# REF-IN-BLE-NS_4-2.net
KiCad netlist of a schematic drawn in EAGLE
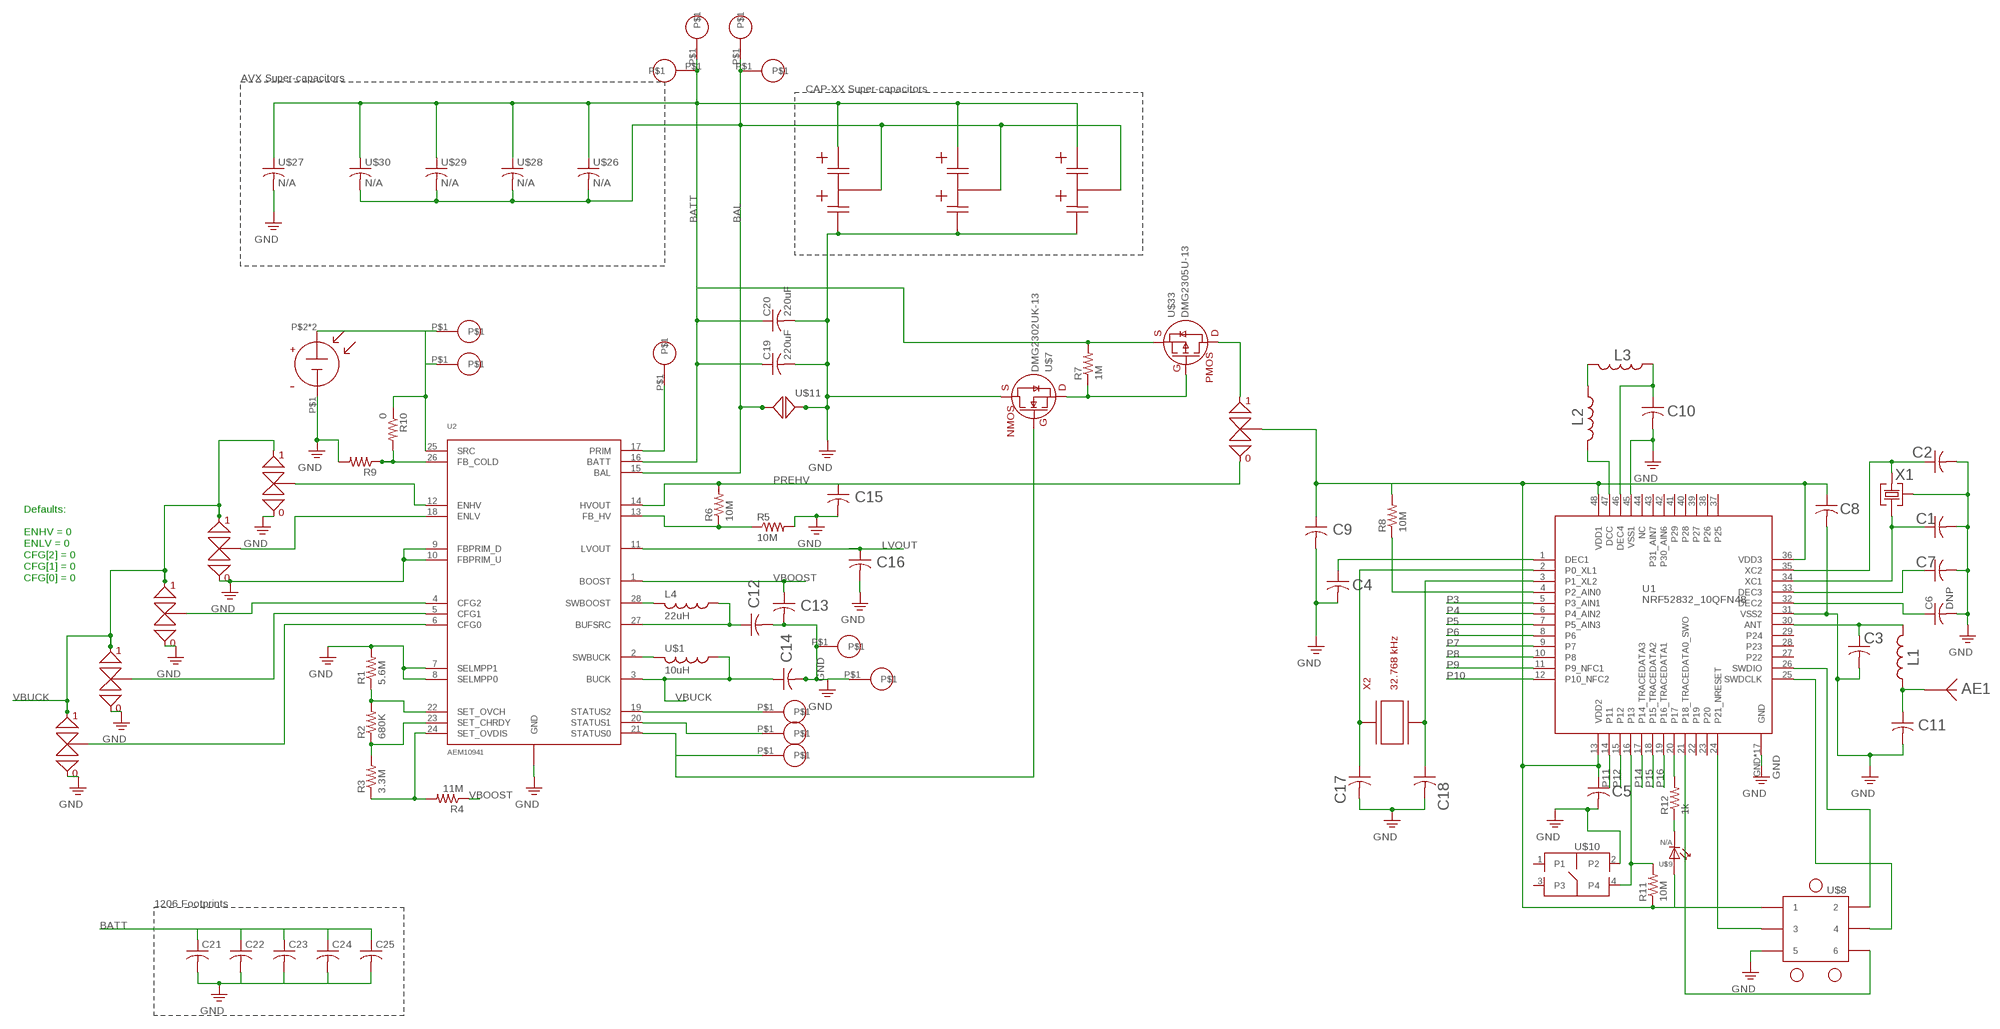
[diagram p0: schematic, sheet 1]

(export (version "E")
  (design (tool "Eeschema 10.0.6"))
  (components
    (comp (ref "AE1")
      (value "2.4GHZ_ANTENNAFLIPPED")
      (footprint "eagle-import:BLE_ANTENNA_NORDIC_FLIPPED")
      (libsource (lib "eagle-import") (part "2.4GHZ_ANTENNAFLIPPED"))
    )
    (comp (ref "C1")
      (value "12pF")
      (footprint "eagle-import:C0603")
      (fields (field (name "MFG_PART#") "C0603C120J5GACTU"))
      (libsource (lib "eagle-import") (part "C-USC0603T-12PF"))
    )
    (comp (ref "C2")
      (value "12pF")
      (footprint "eagle-import:C0603")
      (fields (field (name "MFG_PART#") "C0603C120J5GACTU"))
      (libsource (lib "eagle-import") (part "C-USC0603T-12PF"))
    )
    (comp (ref "C3")
      (value "0.8pF")
      (footprint "eagle-import:C0603")
      (fields (field (name "MFG_PART#") "CBR06C808B5GAC "))
      (libsource (lib "eagle-import") (part "C-USC0603T-0.8PF"))
    )
    (comp (ref "C4")
      (value "100nF")
      (footprint "eagle-import:C0603")
      (fields (field (name "MFG_PART#") "CL10B104KB8NNNC"))
      (libsource (lib "eagle-import") (part "C-USC0603T-100NF"))
    )
    (comp (ref "C5")
      (value "100nF")
      (footprint "eagle-import:C0603")
      (fields (field (name "MFG_PART#") "CL10B104KB8NNNC"))
      (libsource (lib "eagle-import") (part "C-USC0603T-100NF"))
    )
    (comp (ref "C6")
      (value "DNP")
      (footprint "eagle-import:C0603")
      (libsource (lib "eagle-import") (part "C-USC0603"))
    )
    (comp (ref "C7")
      (value "100pF")
      (footprint "eagle-import:C0603")
      (fields (field (name "MFG_PART#") "CL10C101JB8NNNC"))
      (libsource (lib "eagle-import") (part "C-USC0603T-100PF"))
    )
    (comp (ref "C8")
      (value "100nF")
      (footprint "eagle-import:C0603")
      (fields (field (name "MFG_PART#") "CL10B104KB8NNNC"))
      (libsource (lib "eagle-import") (part "C-USC0603T-100NF"))
    )
    (comp (ref "C9")
      (value "4.7uF")
      (footprint "eagle-import:C0603")
      (fields (field (name "MFG_PART#") "CL10A475KQ8NNWC "))
      (libsource (lib "eagle-import") (part "C-USC0603T-4.7UF"))
    )
    (comp (ref "C10")
      (value "1uF")
      (footprint "eagle-import:C0603")
      (fields (field (name "MFG_PART#") "CL10A105KP8NNNC ") (field (name "PERCENTAGE") "10%"))
      (libsource (lib "eagle-import") (part "C-USC0603T-1UF"))
    )
    (comp (ref "C11")
      (value "DNP")
      (footprint "eagle-import:C0603")
      (libsource (lib "eagle-import") (part "C-USC0603"))
    )
    (comp (ref "C12")
      (value "10uF")
      (footprint "eagle-import:C0603")
      (fields (field (name "MFG_PART#") "GRM188R61E106MA73D"))
      (libsource (lib "eagle-import") (part "C-USC0603T-10UF"))
    )
    (comp (ref "C13")
      (value "22uF")
      (footprint "eagle-import:C0603")
      (fields (field (name "MFG_PART#") "GRM188R61A226ME15D"))
      (libsource (lib "eagle-import") (part "C-USC0603T-22UF"))
    )
    (comp (ref "C14")
      (value "10uF")
      (footprint "eagle-import:C0603")
      (fields (field (name "MFG_PART#") "GRM188R61E106MA73D"))
      (libsource (lib "eagle-import") (part "C-USC0603T-10UF"))
    )
    (comp (ref "C15")
      (value "10uF")
      (footprint "eagle-import:C0603")
      (fields (field (name "MFG_PART#") "GRM188R61E106MA73D"))
      (libsource (lib "eagle-import") (part "C-USC0603T-10UF"))
    )
    (comp (ref "C16")
      (value "10uF")
      (footprint "eagle-import:C0603")
      (fields (field (name "MFG_PART#") "GRM188R61E106MA73D"))
      (libsource (lib "eagle-import") (part "C-USC0603T-10UF"))
    )
    (comp (ref "C17")
      (value "12pF")
      (footprint "eagle-import:C0603")
      (fields (field (name "MFG_PART#") "C0603C120J5GACTU"))
      (libsource (lib "eagle-import") (part "C-USC0603T-12PF"))
    )
    (comp (ref "C18")
      (value "12pF")
      (footprint "eagle-import:C0603")
      (fields (field (name "MFG_PART#") "C0603C120J5GACTU"))
      (libsource (lib "eagle-import") (part "C-USC0603T-12PF"))
    )
    (comp (ref "C19")
      (value "220uF")
      (footprint "eagle-import:C1206")
      (fields (field (name "MFG_PART#") "GRM31CC80G227ME11L"))
      (libsource (lib "eagle-import") (part "C-USC1206T-220UF"))
    )
    (comp (ref "C20")
      (value "220uF")
      (footprint "eagle-import:C1206")
      (fields (field (name "MFG_PART#") "GRM31CC80G227ME11L"))
      (libsource (lib "eagle-import") (part "C-USC1206T-220UF"))
    )
    (comp (ref "C21")
      (value "C-USC1206")
      (footprint "eagle-import:C1206")
      (libsource (lib "eagle-import") (part "C-USC1206"))
    )
    (comp (ref "C22")
      (value "C-USC1206")
      (footprint "eagle-import:C1206")
      (libsource (lib "eagle-import") (part "C-USC1206"))
    )
    (comp (ref "C23")
      (value "C-USC1206")
      (footprint "eagle-import:C1206")
      (libsource (lib "eagle-import") (part "C-USC1206"))
    )
    (comp (ref "C24")
      (value "C-USC1206")
      (footprint "eagle-import:C1206")
      (libsource (lib "eagle-import") (part "C-USC1206"))
    )
    (comp (ref "C25")
      (value "C-USC1206")
      (footprint "eagle-import:C1206")
      (libsource (lib "eagle-import") (part "C-USC1206"))
    )
    (comp (ref "L1")
      (value "3.9nH")
      (footprint "eagle-import:L0603")
      (fields (field (name "MFG_PART#") "L-14C3N9SV4T "))
      (libsource (lib "eagle-import") (part "L0603V-3.9NH"))
    )
    (comp (ref "L2")
      (value "10uH")
      (footprint "eagle-import:L0603")
      (fields (field (name "MFG_PART#") "LBR2012T100M"))
      (libsource (lib "eagle-import") (part "L0603V-10UH"))
    )
    (comp (ref "L3")
      (value "15nH")
      (footprint "eagle-import:L0603")
      (fields (field (name "MFG_PART#") "L-14C15NJV4T"))
      (libsource (lib "eagle-import") (part "L0603V-15NH"))
    )
    (comp (ref "L4")
      (value "22uH")
      (footprint "eagle-import:744031220")
      (fields (field (name "MFG_PART#") "744031220"))
      (libsource (lib "eagle-import") (part "744031220"))
    )
    (comp (ref "R1")
      (value "5.6M")
      (footprint "eagle-import:R0603")
      (libsource (lib "eagle-import") (part "R-US_R0603"))
    )
    (comp (ref "R2")
      (value "680K")
      (footprint "eagle-import:R0603")
      (libsource (lib "eagle-import") (part "R-US_R0603"))
    )
    (comp (ref "R3")
      (value "3.3M")
      (footprint "eagle-import:R0603")
      (libsource (lib "eagle-import") (part "R-US_R0603"))
    )
    (comp (ref "R4")
      (value "11M")
      (footprint "eagle-import:R0603")
      (libsource (lib "eagle-import") (part "R-US_R0603"))
    )
    (comp (ref "R5")
      (value "10M")
      (footprint "eagle-import:R0603")
      (libsource (lib "eagle-import") (part "R-US_R0603"))
    )
    (comp (ref "R6")
      (value "10M")
      (footprint "eagle-import:R0603")
      (libsource (lib "eagle-import") (part "R-US_R0603"))
    )
    (comp (ref "R7")
      (value "1M")
      (footprint "eagle-import:R0603")
      (libsource (lib "eagle-import") (part "R-US_R0603"))
    )
    (comp (ref "R8")
      (value "10M")
      (footprint "eagle-import:R0603")
      (libsource (lib "eagle-import") (part "R-US_R0603"))
    )
    (comp (ref "R9")
      (value "R-US_R0603")
      (footprint "eagle-import:R0603")
      (libsource (lib "eagle-import") (part "R-US_R0603"))
    )
    (comp (ref "R10")
      (value "0")
      (footprint "eagle-import:R0603")
      (libsource (lib "eagle-import") (part "R-US_R0603"))
    )
    (comp (ref "R11")
      (value "10M")
      (footprint "eagle-import:R0603")
      (libsource (lib "eagle-import") (part "R-US_R0603"))
    )
    (comp (ref "R12")
      (value "1k")
      (footprint "eagle-import:R0603")
      (libsource (lib "eagle-import") (part "R-US_R0603"))
    )
    (comp (ref "U$1")
      (value "10uH")
      (footprint "eagle-import:L0603")
      (fields (field (name "MFG_PART#") "LBR2012T100M"))
      (libsource (lib "eagle-import") (part "L0603V-10UH"))
    )
    (comp (ref "U$2")
      (value "DOUBLE_SOLDER_BRIDGE0_PASTED")
      (footprint "eagle-import:DOUBLE_SOLDER_BRIDGE_0_PASTED")
      (libsource (lib "eagle-import") (part "DOUBLE_SOLDER_BRIDGE0_PASTED"))
    )
    (comp (ref "U$3")
      (value "DOUBLE_SOLDER_BRIDGE0_PASTED")
      (footprint "eagle-import:DOUBLE_SOLDER_BRIDGE_0_PASTED")
      (libsource (lib "eagle-import") (part "DOUBLE_SOLDER_BRIDGE0_PASTED"))
    )
    (comp (ref "U$4")
      (value "DOUBLE_SOLDER_BRIDGE0_PASTED")
      (footprint "eagle-import:DOUBLE_SOLDER_BRIDGE_0_PASTED")
      (libsource (lib "eagle-import") (part "DOUBLE_SOLDER_BRIDGE0_PASTED"))
    )
    (comp (ref "U$5")
      (value "DOUBLE_SOLDER_BRIDGE0_PASTED")
      (footprint "eagle-import:DOUBLE_SOLDER_BRIDGE_0_PASTED")
      (libsource (lib "eagle-import") (part "DOUBLE_SOLDER_BRIDGE0_PASTED"))
    )
    (comp (ref "U$6")
      (value "DOUBLE_SOLDER_BRIDGE0_PASTED")
      (footprint "eagle-import:DOUBLE_SOLDER_BRIDGE_0_PASTED")
      (libsource (lib "eagle-import") (part "DOUBLE_SOLDER_BRIDGE0_PASTED"))
    )
    (comp (ref "U$7")
      (value "DMG2302UK-13")
      (footprint "eagle-import:SOT-23-3-DIODESINC")
      (libsource (lib "eagle-import") (part "DMG2302UK-13"))
    )
    (comp (ref "U$8")
      (value "N/A")
      (footprint "eagle-import:TC2030-IDC")
      (libsource (lib "eagle-import") (part "TC2030-IDC"))
    )
    (comp (ref "U$9")
      (value "N/A")
      (footprint "eagle-import:APT1608LZGCK")
      (fields (field (name "MFG_PART#") "APT1608LZGCK"))
      (libsource (lib "eagle-import") (part "APT1608LZGCK"))
    )
    (comp (ref "U$10")
      (value "MJTP1140")
      (footprint "eagle-import:MJTP1140A")
      (fields (field (name "MFG_PART#") "TL3315NF100Q "))
      (libsource (lib "eagle-import") (part "MJTP1140"))
    )
    (comp (ref "U$11")
      (value "SOLDER_BRIGDECLOSED")
      (footprint "eagle-import:SOLDER_BRIDGE_CLOSED")
      (libsource (lib "eagle-import") (part "SOLDER_BRIGDECLOSED"))
    )
    (comp (ref "U$12")
      (value "N/A")
      (footprint "eagle-import:1MM_PAD")
      (libsource (lib "eagle-import") (part "1MM_PAD"))
    )
    (comp (ref "U$13")
      (value "N/A")
      (footprint "eagle-import:1MM_PAD")
      (libsource (lib "eagle-import") (part "1MM_PAD"))
    )
    (comp (ref "U$14")
      (value "N/A")
      (footprint "eagle-import:1MM_PAD")
      (libsource (lib "eagle-import") (part "1MM_PAD"))
    )
    (comp (ref "U$15")
      (value "N/A")
      (footprint "eagle-import:1MM_PAD")
      (libsource (lib "eagle-import") (part "1MM_PAD"))
    )
    (comp (ref "U$16")
      (value "N/A")
      (footprint "eagle-import:SOLAR_CELL_37X54MM")
      (libsource (lib "eagle-import") (part "SOLAR_CELL_LL200-2.4-37"))
    )
    (comp (ref "U$17")
      (value "N/A")
      (footprint "eagle-import:1MM_PAD")
      (libsource (lib "eagle-import") (part "1MM_PAD"))
    )
    (comp (ref "U$18")
      (value "N/A")
      (footprint "eagle-import:1MM_PAD")
      (libsource (lib "eagle-import") (part "1MM_PAD"))
    )
    (comp (ref "U$19")
      (value "N/A")
      (footprint "eagle-import:1MM_PAD")
      (libsource (lib "eagle-import") (part "1MM_PAD"))
    )
    (comp (ref "U$23")
      (value "N/A")
      (footprint "eagle-import:CAP-XX_A-TYPE")
      (libsource (lib "eagle-import") (part "CAP-XX_A-TYPE"))
    )
    (comp (ref "U$24")
      (value "N/A")
      (footprint "eagle-import:CAP-XX_S-TYPE")
      (libsource (lib "eagle-import") (part "CAP-XX_S-TYPE"))
    )
    (comp (ref "U$25")
      (value "N/A")
      (footprint "eagle-import:CAP-XX_W-TYPE")
      (libsource (lib "eagle-import") (part "CAP-XX_W-TYPE"))
    )
    (comp (ref "U$26")
      (value "N/A")
      (footprint "eagle-import:BZ01_L-TYPE")
      (libsource (lib "eagle-import") (part "BZ01_L-TYPE"))
    )
    (comp (ref "U$27")
      (value "N/A")
      (footprint "eagle-import:BZ059_N-TYPE")
      (libsource (lib "eagle-import") (part "BZ059_N-TYPE"))
    )
    (comp (ref "U$28")
      (value "N/A")
      (footprint "eagle-import:BZ01_S-TYPE")
      (libsource (lib "eagle-import") (part "BZ01_S-TYPE"))
    )
    (comp (ref "U$29")
      (value "N/A")
      (footprint "eagle-import:BZ05_S-TYPE")
      (libsource (lib "eagle-import") (part "BZ05_S-TYPE"))
    )
    (comp (ref "U$30")
      (value "N/A")
      (footprint "eagle-import:BZ09_S-TYPE")
      (libsource (lib "eagle-import") (part "BZ09_S-TYPE"))
    )
    (comp (ref "U$31")
      (value "DOUBLE_SOLDER_BRIDGE1_PASTED")
      (footprint "eagle-import:DOUBLE_SOLDER_BRIDGE_1_PASTED")
      (libsource (lib "eagle-import") (part "DOUBLE_SOLDER_BRIDGE1_PASTED"))
    )
    (comp (ref "U$33")
      (value "DMG2305U-13")
      (footprint "eagle-import:SOT-23-3-DIODESINC")
      (libsource (lib "eagle-import") (part "DMG2305U-13"))
    )
    (comp (ref "U$35")
      (value "N/A")
      (footprint "eagle-import:1MM_PAD")
      (libsource (lib "eagle-import") (part "1MM_PAD"))
    )
    (comp (ref "U$36")
      (value "N/A")
      (footprint "eagle-import:1MM_PAD")
      (libsource (lib "eagle-import") (part "1MM_PAD"))
    )
    (comp (ref "U$39")
      (value "N/A")
      (footprint "eagle-import:1MM_PAD")
      (libsource (lib "eagle-import") (part "1MM_PAD"))
    )
    (comp (ref "U$40")
      (value "N/A")
      (footprint "eagle-import:1MM_PAD")
      (libsource (lib "eagle-import") (part "1MM_PAD"))
    )
    (comp (ref "U$41")
      (value "N/A")
      (footprint "eagle-import:1MM_PAD")
      (libsource (lib "eagle-import") (part "1MM_PAD"))
    )
    (comp (ref "U1")
      (value "NRF52832_10QFN48")
      (footprint "eagle-import:NRF52832_10")
      (fields (field (name "MFG_PART#") "NRF52832-QFAA-R"))
      (libsource (lib "eagle-import") (part "NRF52832_10QFN48"))
    )
    (comp (ref "U2")
      (value "AEM10941")
      (footprint "eagle-import:QFN28_5X5_05PITCH")
      (fields (field (name "MFG_PART#") "AEM10941-QFN "))
      (libsource (lib "eagle-import") (part "AEM10941"))
    )
    (comp (ref "X1")
      (value "32 MHz")
      (footprint "eagle-import:FA-128-EPSON")
      (fields (field (name "MFG_PART#") "FA-128 32.0000MF10Z-AJ3"))
      (libsource (lib "eagle-import") (part "FA-128-32MHZMF10Z-AJ5"))
    )
    (comp (ref "X2")
      (value "32.768 kHz")
      (footprint "eagle-import:FC-135")
      (fields (field (name "MFG_PART#") "FC-135 32.7680KA-AC"))
      (libsource (lib "eagle-import") (part "FC-135_32.7680KA-AC"))
    )
  )
  (nets
    (net (code "1") (name "/BAL") (class "Default")
      (node (ref "U$11") (pin "P$1") (pinfunction "P1_P$1") (pintype "bidirectional"))
      (node (ref "U$19") (pin "P$1") (pinfunction "P$1_P$1") (pintype "bidirectional"))
      (node (ref "U$23") (pin "P$1") (pinfunction "BAL_P$1") (pintype "bidirectional"))
      (node (ref "U$24") (pin "P$1") (pinfunction "BAL_P$1") (pintype "bidirectional"))
      (node (ref "U$25") (pin "P$1") (pinfunction "BAL_P$1") (pintype "bidirectional"))
      (node (ref "U$26") (pin "P$3") (pinfunction "2_P$3") (pintype "passive"))
      (node (ref "U$26") (pin "P$4") (pinfunction "2_P$4") (pintype "passive"))
      (node (ref "U$28") (pin "P$3") (pinfunction "2_P$3") (pintype "passive"))
      (node (ref "U$29") (pin "P$3") (pinfunction "2_P$3") (pintype "passive"))
      (node (ref "U$30") (pin "P$3") (pinfunction "2_P$3") (pintype "passive"))
      (node (ref "U$41") (pin "P$1") (pinfunction "P$1_P$1") (pintype "bidirectional"))
      (node (ref "U2") (pin "15") (pinfunction "BAL_15") (pintype "bidirectional"))
    )
    (net (code "2") (name "/BATT") (class "Default")
      (node (ref "C19") (pin "1") (pinfunction "1_1") (pintype "passive"))
      (node (ref "C20") (pin "1") (pinfunction "1_1") (pintype "passive"))
      (node (ref "C21") (pin "1") (pinfunction "1_1") (pintype "passive"))
      (node (ref "C22") (pin "1") (pinfunction "1_1") (pintype "passive"))
      (node (ref "C23") (pin "1") (pinfunction "1_1") (pintype "passive"))
      (node (ref "C24") (pin "1") (pinfunction "1_1") (pintype "passive"))
      (node (ref "C25") (pin "1") (pinfunction "1_1") (pintype "passive"))
      (node (ref "R7") (pin "2") (pinfunction "2_2") (pintype "passive"))
      (node (ref "U$18") (pin "P$1") (pinfunction "P$1_P$1") (pintype "bidirectional"))
      (node (ref "U$23") (pin "P$2") (pinfunction "+_P$2") (pintype "bidirectional"))
      (node (ref "U$24") (pin "P$2") (pinfunction "+_P$2") (pintype "bidirectional"))
      (node (ref "U$25") (pin "P$2") (pinfunction "+_P$2") (pintype "bidirectional"))
      (node (ref "U$26") (pin "P$1") (pinfunction "1_P$1") (pintype "passive"))
      (node (ref "U$26") (pin "P$2") (pinfunction "1_P$2") (pintype "passive"))
      (node (ref "U$27") (pin "P$1") (pinfunction "1_P$1") (pintype "passive"))
      (node (ref "U$28") (pin "P$1") (pinfunction "1_P$1") (pintype "passive"))
      (node (ref "U$28") (pin "P$2") (pinfunction "1_P$2") (pintype "passive"))
      (node (ref "U$29") (pin "P$1") (pinfunction "1_P$1") (pintype "passive"))
      (node (ref "U$29") (pin "P$2") (pinfunction "1_P$2") (pintype "passive"))
      (node (ref "U$30") (pin "P$1") (pinfunction "1_P$1") (pintype "passive"))
      (node (ref "U$30") (pin "P$2") (pinfunction "1_P$2") (pintype "passive"))
      (node (ref "U$33") (pin "2") (pinfunction "S_2") (pintype "bidirectional"))
      (node (ref "U$40") (pin "P$1") (pinfunction "P$1_P$1") (pintype "bidirectional"))
      (node (ref "U2") (pin "16") (pinfunction "BATT_16") (pintype "bidirectional"))
    )
    (net (code "3") (name "/LVOUT") (class "Default")
      (node (ref "C16") (pin "1") (pinfunction "1_1") (pintype "passive"))
      (node (ref "U2") (pin "11") (pinfunction "LVOUT_11") (pintype "output"))
    )
    (net (code "4") (name "/P3") (class "Default")
      (node (ref "U1") (pin "5") (pinfunction "P3_AIN1_5") (pintype "bidirectional"))
    )
    (net (code "5") (name "/P4") (class "Default")
      (node (ref "U1") (pin "6") (pinfunction "P4_AIN2_6") (pintype "bidirectional"))
    )
    (net (code "6") (name "/P5") (class "Default")
      (node (ref "U1") (pin "7") (pinfunction "P5_AIN3_7") (pintype "bidirectional"))
    )
    (net (code "7") (name "/P6") (class "Default")
      (node (ref "U1") (pin "8") (pinfunction "P6_8") (pintype "bidirectional"))
    )
    (net (code "8") (name "/P7") (class "Default")
      (node (ref "U1") (pin "9") (pinfunction "P7_9") (pintype "bidirectional"))
    )
    (net (code "9") (name "/P8") (class "Default")
      (node (ref "U1") (pin "10") (pinfunction "P8_10") (pintype "bidirectional"))
    )
    (net (code "10") (name "/P9") (class "Default")
      (node (ref "U1") (pin "11") (pinfunction "P9_NFC1_11") (pintype "bidirectional"))
    )
    (net (code "11") (name "/P10") (class "Default")
      (node (ref "U1") (pin "12") (pinfunction "P10_NFC2_12") (pintype "bidirectional"))
    )
    (net (code "12") (name "/P11") (class "Default")
      (node (ref "U1") (pin "14") (pinfunction "P11_14") (pintype "bidirectional"))
    )
    (net (code "13") (name "/P12") (class "Default")
      (node (ref "U1") (pin "15") (pinfunction "P12_15") (pintype "bidirectional"))
    )
    (net (code "14") (name "/P14") (class "Default")
      (node (ref "U1") (pin "17") (pinfunction "P14_TRACEDATA3_17") (pintype "bidirectional"))
    )
    (net (code "15") (name "/P15") (class "Default")
      (node (ref "U1") (pin "18") (pinfunction "P15_TRACEDATA2_18") (pintype "bidirectional"))
    )
    (net (code "16") (name "/P16") (class "Default")
      (node (ref "U1") (pin "19") (pinfunction "P16_TRACEDATA1_19") (pintype "bidirectional"))
    )
    (net (code "17") (name "/PREHV") (class "Default")
      (node (ref "C15") (pin "1") (pinfunction "1_1") (pintype "passive"))
      (node (ref "R6") (pin "2") (pinfunction "2_2") (pintype "passive"))
      (node (ref "U$31") (pin "IN0") (pinfunction "IN0_IN0") (pintype "bidirectional"))
      (node (ref "U2") (pin "14") (pinfunction "HVOUT_14") (pintype "output"))
    )
    (net (code "18") (name "/VBOOST") (class "Default")
      (node (ref "C13") (pin "1") (pinfunction "1_1") (pintype "passive"))
      (node (ref "R4") (pin "1") (pinfunction "1_1") (pintype "passive"))
      (node (ref "U2") (pin "1") (pinfunction "BOOST_1") (pintype "bidirectional"))
    )
    (net (code "19") (name "/VBUCK") (class "Default")
      (node (ref "C14") (pin "1") (pinfunction "1_1") (pintype "passive"))
      (node (ref "U$1") (pin "1") (pinfunction "1_1") (pintype "passive"))
      (node (ref "U$2") (pin "IN1") (pinfunction "IN1_IN1") (pintype "bidirectional"))
      (node (ref "U$3") (pin "IN1") (pinfunction "IN1_IN1") (pintype "bidirectional"))
      (node (ref "U$4") (pin "IN1") (pinfunction "IN1_IN1") (pintype "bidirectional"))
      (node (ref "U$5") (pin "IN1") (pinfunction "IN1_IN1") (pintype "bidirectional"))
      (node (ref "U$6") (pin "IN1") (pinfunction "IN1_IN1") (pintype "bidirectional"))
      (node (ref "U2") (pin "3") (pinfunction "BUCK_3") (pintype "bidirectional"))
    )
    (net (code "20") (name "GND") (class "Default")
      (node (ref "C1") (pin "2") (pinfunction "2_2") (pintype "passive"))
      (node (ref "C10") (pin "2") (pinfunction "2_2") (pintype "passive"))
      (node (ref "C11") (pin "2") (pinfunction "2_2") (pintype "passive"))
      (node (ref "C12") (pin "2") (pinfunction "2_2") (pintype "passive"))
      (node (ref "C13") (pin "2") (pinfunction "2_2") (pintype "passive"))
      (node (ref "C14") (pin "2") (pinfunction "2_2") (pintype "passive"))
      (node (ref "C15") (pin "2") (pinfunction "2_2") (pintype "passive"))
      (node (ref "C16") (pin "2") (pinfunction "2_2") (pintype "passive"))
      (node (ref "C17") (pin "2") (pinfunction "2_2") (pintype "passive"))
      (node (ref "C18") (pin "2") (pinfunction "2_2") (pintype "passive"))
      (node (ref "C19") (pin "2") (pinfunction "2_2") (pintype "passive"))
      (node (ref "C2") (pin "2") (pinfunction "2_2") (pintype "passive"))
      (node (ref "C20") (pin "2") (pinfunction "2_2") (pintype "passive"))
      (node (ref "C21") (pin "2") (pinfunction "2_2") (pintype "passive"))
      (node (ref "C22") (pin "2") (pinfunction "2_2") (pintype "passive"))
      (node (ref "C23") (pin "2") (pinfunction "2_2") (pintype "passive"))
      (node (ref "C24") (pin "2") (pinfunction "2_2") (pintype "passive"))
      (node (ref "C25") (pin "2") (pinfunction "2_2") (pintype "passive"))
      (node (ref "C3") (pin "2") (pinfunction "2_2") (pintype "passive"))
      (node (ref "C4") (pin "2") (pinfunction "2_2") (pintype "passive"))
      (node (ref "C5") (pin "2") (pinfunction "2_2") (pintype "passive"))
      (node (ref "C6") (pin "2") (pinfunction "2_2") (pintype "passive"))
      (node (ref "C7") (pin "2") (pinfunction "2_2") (pintype "passive"))
      (node (ref "C8") (pin "2") (pinfunction "2_2") (pintype "passive"))
      (node (ref "C9") (pin "2") (pinfunction "2_2") (pintype "passive"))
      (node (ref "R1") (pin "2") (pinfunction "2_2") (pintype "passive"))
      (node (ref "R5") (pin "2") (pinfunction "2_2") (pintype "passive"))
      (node (ref "R9") (pin "2") (pinfunction "2_2") (pintype "passive"))
      (node (ref "U$10") (pin "2") (pinfunction "P2_2") (pintype "bidirectional"))
      (node (ref "U$11") (pin "P$2") (pinfunction "P2_P$2") (pintype "bidirectional"))
      (node (ref "U$16") (pin "P$1") (pinfunction "GND_P$1") (pintype "bidirectional"))
      (node (ref "U$17") (pin "P$1") (pinfunction "P$1_P$1") (pintype "bidirectional"))
      (node (ref "U$2") (pin "IN0") (pinfunction "IN0_IN0") (pintype "bidirectional"))
      (node (ref "U$23") (pin "P$3") (pinfunction "-_P$3") (pintype "bidirectional"))
      (node (ref "U$24") (pin "P$3") (pinfunction "-_P$3") (pintype "bidirectional"))
      (node (ref "U$25") (pin "P$3") (pinfunction "-_P$3") (pintype "bidirectional"))
      (node (ref "U$27") (pin "P$2") (pinfunction "2_P$2") (pintype "passive"))
      (node (ref "U$3") (pin "IN0") (pinfunction "IN0_IN0") (pintype "bidirectional"))
      (node (ref "U$35") (pin "P$1") (pinfunction "P$1_P$1") (pintype "bidirectional"))
      (node (ref "U$4") (pin "IN0") (pinfunction "IN0_IN0") (pintype "bidirectional"))
      (node (ref "U$5") (pin "IN0") (pinfunction "IN0_IN0") (pintype "bidirectional"))
      (node (ref "U$6") (pin "IN0") (pinfunction "IN0_IN0") (pintype "bidirectional"))
      (node (ref "U$7") (pin "2") (pinfunction "S_2") (pintype "bidirectional"))
      (node (ref "U$8") (pin "P5") (pinfunction "5_P5") (pintype "bidirectional"))
      (node (ref "U1") (pin "31") (pinfunction "VSS2_31") (pintype "bidirectional"))
      (node (ref "U1") (pin "45") (pinfunction "VSS1_45") (pintype "bidirectional"))
      (node (ref "U1") (pin "GND") (pinfunction "GND_GND") (pintype "bidirectional"))
      (node (ref "U1") (pin "P$10") (pinfunction "GND_P$10") (pintype "bidirectional"))
      (node (ref "U1") (pin "P$11") (pinfunction "GND_P$11") (pintype "bidirectional"))
      (node (ref "U1") (pin "P$12") (pinfunction "GND_P$12") (pintype "bidirectional"))
      (node (ref "U1") (pin "P$13") (pinfunction "GND_P$13") (pintype "bidirectional"))
      (node (ref "U1") (pin "P$14") (pinfunction "GND_P$14") (pintype "bidirectional"))
      (node (ref "U1") (pin "P$15") (pinfunction "GND_P$15") (pintype "bidirectional"))
      (node (ref "U1") (pin "P$16") (pinfunction "GND_P$16") (pintype "bidirectional"))
      (node (ref "U1") (pin "P$17") (pinfunction "GND_P$17") (pintype "bidirectional"))
      (node (ref "U1") (pin "P$2") (pinfunction "GND_P$2") (pintype "bidirectional"))
      (node (ref "U1") (pin "P$3") (pinfunction "GND_P$3") (pintype "bidirectional"))
      (node (ref "U1") (pin "P$4") (pinfunction "GND_P$4") (pintype "bidirectional"))
      (node (ref "U1") (pin "P$5") (pinfunction "GND_P$5") (pintype "bidirectional"))
      (node (ref "U1") (pin "P$6") (pinfunction "GND_P$6") (pintype "bidirectional"))
      (node (ref "U1") (pin "P$7") (pinfunction "GND_P$7") (pintype "bidirectional"))
      (node (ref "U1") (pin "P$8") (pinfunction "GND_P$8") (pintype "bidirectional"))
      (node (ref "U1") (pin "P$9") (pinfunction "GND_P$9") (pintype "bidirectional"))
      (node (ref "U2") (pin "10") (pinfunction "FBPRIM_U_10") (pintype "bidirectional"))
      (node (ref "U2") (pin "7") (pinfunction "SELMPP1_7") (pintype "input"))
      (node (ref "U2") (pin "8") (pinfunction "SELMPP0_8") (pintype "input"))
      (node (ref "U2") (pin "9") (pinfunction "FBPRIM_D_9") (pintype "bidirectional"))
      (node (ref "U2") (pin "GND") (pinfunction "GND_GND") (pintype "power_in"))
      (node (ref "U2") (pin "GND1") (pinfunction "GND_GND1") (pintype "power_in"))
      (node (ref "U2") (pin "GND2") (pinfunction "GND_GND2") (pintype "power_in"))
      (node (ref "U2") (pin "GND3") (pinfunction "GND_GND3") (pintype "power_in"))
      (node (ref "U2") (pin "GND4") (pinfunction "GND_GND4") (pintype "power_in"))
      (node (ref "U2") (pin "GND5") (pinfunction "GND_GND5") (pintype "power_in"))
      (node (ref "X1") (pin "P2") (pinfunction "P3_P2") (pintype "bidirectional"))
      (node (ref "X1") (pin "P4") (pinfunction "P3_P4") (pintype "bidirectional"))
    )
    (net (code "21") (name "Net-(AE1-PadP$1)") (class "Default")
      (node (ref "AE1") (pin "P$1") (pinfunction "P$1_P$1") (pintype "bidirectional"))
      (node (ref "C11") (pin "1") (pinfunction "1_1") (pintype "passive"))
      (node (ref "L1") (pin "1") (pinfunction "1_1") (pintype "passive"))
    )
    (net (code "22") (name "Net-(L2-Pad1)") (class "Default")
      (node (ref "L2") (pin "1") (pinfunction "1_1") (pintype "passive"))
      (node (ref "L3") (pin "2") (pinfunction "2_2") (pintype "passive"))
    )
    (net (code "23") (name "Net-(L4-1)") (class "Default")
      (node (ref "C12") (pin "1") (pinfunction "1_1") (pintype "passive"))
      (node (ref "L4") (pin "PIN1") (pinfunction "1_PIN1") (pintype "passive"))
      (node (ref "U2") (pin "27") (pinfunction "BUFSRC_27") (pintype "bidirectional"))
    )
    (net (code "24") (name "Net-(L4-2)") (class "Default")
      (node (ref "L4") (pin "PIN2") (pinfunction "2_PIN2") (pintype "passive"))
      (node (ref "U2") (pin "28") (pinfunction "SWBOOST_28") (pintype "bidirectional"))
    )
    (net (code "25") (name "Net-(R12-Pad1)") (class "Default")
      (node (ref "R12") (pin "1") (pinfunction "1_1") (pintype "passive"))
      (node (ref "U$9") (pin "C") (pinfunction "C_C") (pintype "bidirectional"))
    )
    (net (code "26") (name "Net-(U$7-G)") (class "Default")
      (node (ref "U$15") (pin "P$1") (pinfunction "P$1_P$1") (pintype "bidirectional"))
      (node (ref "U$7") (pin "1") (pinfunction "G_1") (pintype "bidirectional"))
      (node (ref "U2") (pin "21") (pinfunction "STATUS0_21") (pintype "output"))
    )
    (net (code "27") (name "Net-(U$8-1)") (class "Default")
      (node (ref "C5") (pin "1") (pinfunction "1_1") (pintype "passive"))
      (node (ref "C8") (pin "1") (pinfunction "1_1") (pintype "passive"))
      (node (ref "C9") (pin "1") (pinfunction "1_1") (pintype "passive"))
      (node (ref "R11") (pin "1") (pinfunction "1_1") (pintype "passive"))
      (node (ref "R8") (pin "2") (pinfunction "2_2") (pintype "passive"))
      (node (ref "U$31") (pin "OUT") (pinfunction "OUT_OUT") (pintype "bidirectional"))
      (node (ref "U$8") (pin "P1") (pinfunction "1_P1") (pintype "bidirectional"))
      (node (ref "U$9") (pin "A") (pinfunction "A_A") (pintype "bidirectional"))
      (node (ref "U1") (pin "13") (pinfunction "VDD2_13") (pintype "bidirectional"))
      (node (ref "U1") (pin "36") (pinfunction "VDD3_36") (pintype "bidirectional"))
      (node (ref "U1") (pin "48") (pinfunction "VDD1_48") (pintype "bidirectional"))
    )
    (net (code "28") (name "Net-(U$8-2)") (class "Default")
      (node (ref "U$8") (pin "P2") (pinfunction "2_P2") (pintype "bidirectional"))
      (node (ref "U1") (pin "26") (pinfunction "SWDIO_26") (pintype "bidirectional"))
    )
    (net (code "29") (name "Net-(U$8-3)") (class "Default")
      (node (ref "U$8") (pin "P3") (pinfunction "3_P3") (pintype "bidirectional"))
      (node (ref "U1") (pin "24") (pinfunction "P21_NRESET_24") (pintype "bidirectional"))
    )
    (net (code "30") (name "Net-(U$8-4)") (class "Default")
      (node (ref "U$8") (pin "P4") (pinfunction "4_P4") (pintype "bidirectional"))
      (node (ref "U1") (pin "25") (pinfunction "SWDCLK_25") (pintype "bidirectional"))
    )
    (net (code "31") (name "Net-(U$8-6)") (class "Default")
      (node (ref "U$8") (pin "P6") (pinfunction "6_P6") (pintype "bidirectional"))
      (node (ref "U1") (pin "21") (pinfunction "P18_TRACEDATA0_SWO_21") (pintype "bidirectional"))
    )
    (net (code "32") (name "Net-(U$10-P4)") (class "Default")
      (node (ref "R11") (pin "2") (pinfunction "2_2") (pintype "passive"))
      (node (ref "U$10") (pin "4") (pinfunction "P4_4") (pintype "bidirectional"))
      (node (ref "U1") (pin "16") (pinfunction "P13_16") (pintype "bidirectional"))
    )
    (net (code "33") (name "Net-(U$33-D)") (class "Default")
      (node (ref "U$31") (pin "IN1") (pinfunction "IN1_IN1") (pintype "bidirectional"))
      (node (ref "U$33") (pin "3") (pinfunction "D_3") (pintype "bidirectional"))
    )
    (net (code "34") (name "Net-(U$33-G)") (class "Default")
      (node (ref "R7") (pin "1") (pinfunction "1_1") (pintype "passive"))
      (node (ref "U$33") (pin "1") (pinfunction "G_1") (pintype "bidirectional"))
      (node (ref "U$7") (pin "3") (pinfunction "D_3") (pintype "bidirectional"))
    )
    (net (code "35") (name "Net-(U1-ANT)") (class "Default")
      (node (ref "C3") (pin "1") (pinfunction "1_1") (pintype "passive"))
      (node (ref "L1") (pin "2") (pinfunction "2_2") (pintype "passive"))
      (node (ref "U1") (pin "30") (pinfunction "ANT_30") (pintype "bidirectional"))
    )
    (net (code "36") (name "Net-(U1-DCC)") (class "Default")
      (node (ref "L2") (pin "2") (pinfunction "2_2") (pintype "passive"))
      (node (ref "U1") (pin "47") (pinfunction "DCC_47") (pintype "bidirectional"))
    )
    (net (code "37") (name "Net-(U1-DEC1)") (class "Default")
      (node (ref "C4") (pin "1") (pinfunction "1_1") (pintype "passive"))
      (node (ref "U1") (pin "1") (pinfunction "DEC1_1") (pintype "bidirectional"))
    )
    (net (code "38") (name "Net-(U1-DEC2)") (class "Default")
      (node (ref "C6") (pin "1") (pinfunction "1_1") (pintype "passive"))
      (node (ref "U1") (pin "32") (pinfunction "DEC2_32") (pintype "bidirectional"))
    )
    (net (code "39") (name "Net-(U1-DEC3)") (class "Default")
      (node (ref "C7") (pin "1") (pinfunction "1_1") (pintype "passive"))
      (node (ref "U1") (pin "33") (pinfunction "DEC3_33") (pintype "bidirectional"))
    )
    (net (code "40") (name "Net-(U1-DEC4)") (class "Default")
      (node (ref "C10") (pin "1") (pinfunction "1_1") (pintype "passive"))
      (node (ref "L3") (pin "1") (pinfunction "1_1") (pintype "passive"))
      (node (ref "U1") (pin "46") (pinfunction "DEC4_46") (pintype "bidirectional"))
    )
    (net (code "41") (name "Net-(U1-P0_XL1)") (class "Default")
      (node (ref "C17") (pin "1") (pinfunction "1_1") (pintype "passive"))
      (node (ref "U1") (pin "2") (pinfunction "P0_XL1_2") (pintype "bidirectional"))
      (node (ref "X2") (pin "P$1") (pinfunction "P$1_P$1") (pintype "bidirectional"))
    )
    (net (code "42") (name "Net-(U1-P1_XL2)") (class "Default")
      (node (ref "C18") (pin "1") (pinfunction "1_1") (pintype "passive"))
      (node (ref "U1") (pin "3") (pinfunction "P1_XL2_3") (pintype "bidirectional"))
      (node (ref "X2") (pin "P$2") (pinfunction "P$2_P$2") (pintype "bidirectional"))
    )
    (net (code "43") (name "Net-(U1-P2_AIN0)") (class "Default")
      (node (ref "R8") (pin "1") (pinfunction "1_1") (pintype "passive"))
      (node (ref "U1") (pin "4") (pinfunction "P2_AIN0_4") (pintype "bidirectional"))
    )
    (net (code "44") (name "Net-(U1-P17)") (class "Default")
      (node (ref "R12") (pin "2") (pinfunction "2_2") (pintype "passive"))
      (node (ref "U1") (pin "20") (pinfunction "P17_20") (pintype "bidirectional"))
    )
    (net (code "45") (name "Net-(U1-XC1)") (class "Default")
      (node (ref "C1") (pin "1") (pinfunction "1_1") (pintype "passive"))
      (node (ref "U1") (pin "34") (pinfunction "XC1_34") (pintype "bidirectional"))
      (node (ref "X1") (pin "P3") (pinfunction "1_P3") (pintype "passive"))
    )
    (net (code "46") (name "Net-(U1-XC2)") (class "Default")
      (node (ref "C2") (pin "1") (pinfunction "1_1") (pintype "passive"))
      (node (ref "U1") (pin "35") (pinfunction "XC2_35") (pintype "bidirectional"))
      (node (ref "X1") (pin "P1") (pinfunction "2_P1") (pintype "passive"))
    )
    (net (code "47") (name "Net-(U2-CFG0)") (class "Default")
      (node (ref "U$6") (pin "OUT") (pinfunction "OUT_OUT") (pintype "bidirectional"))
      (node (ref "U2") (pin "6") (pinfunction "CFG0_6") (pintype "input"))
    )
    (net (code "48") (name "Net-(U2-CFG1)") (class "Default")
      (node (ref "U$5") (pin "OUT") (pinfunction "OUT_OUT") (pintype "bidirectional"))
      (node (ref "U2") (pin "5") (pinfunction "CFG1_5") (pintype "input"))
    )
    (net (code "49") (name "Net-(U2-CFG2)") (class "Default")
      (node (ref "U$4") (pin "OUT") (pinfunction "OUT_OUT") (pintype "bidirectional"))
      (node (ref "U2") (pin "4") (pinfunction "CFG2_4") (pintype "input"))
    )
    (net (code "50") (name "Net-(U2-ENHV)") (class "Default")
      (node (ref "U$2") (pin "OUT") (pinfunction "OUT_OUT") (pintype "bidirectional"))
      (node (ref "U2") (pin "12") (pinfunction "ENHV_12") (pintype "input"))
    )
    (net (code "51") (name "Net-(U2-ENLV)") (class "Default")
      (node (ref "U$3") (pin "OUT") (pinfunction "OUT_OUT") (pintype "bidirectional"))
      (node (ref "U2") (pin "18") (pinfunction "ENLV_18") (pintype "input"))
    )
    (net (code "52") (name "Net-(U2-FB_COLD)") (class "Default")
      (node (ref "R10") (pin "2") (pinfunction "2_2") (pintype "passive"))
      (node (ref "R9") (pin "1") (pinfunction "1_1") (pintype "passive"))
      (node (ref "U2") (pin "26") (pinfunction "FB_COLD_26") (pintype "bidirectional"))
    )
    (net (code "53") (name "Net-(U2-FB_HV)") (class "Default")
      (node (ref "R5") (pin "1") (pinfunction "1_1") (pintype "passive"))
      (node (ref "R6") (pin "1") (pinfunction "1_1") (pintype "passive"))
      (node (ref "U2") (pin "13") (pinfunction "FB_HV_13") (pintype "input"))
    )
    (net (code "54") (name "Net-(U2-PRIM)") (class "Default")
      (node (ref "U$12") (pin "P$1") (pinfunction "P$1_P$1") (pintype "bidirectional"))
      (node (ref "U2") (pin "17") (pinfunction "PRIM_17") (pintype "bidirectional"))
    )
    (net (code "55") (name "Net-(U2-SET_CHRDY)") (class "Default")
      (node (ref "R2") (pin "1") (pinfunction "1_1") (pintype "passive"))
      (node (ref "R3") (pin "2") (pinfunction "2_2") (pintype "passive"))
      (node (ref "U2") (pin "23") (pinfunction "SET_CHRDY_23") (pintype "bidirectional"))
    )
    (net (code "56") (name "Net-(U2-SET_OVCH)") (class "Default")
      (node (ref "R1") (pin "1") (pinfunction "1_1") (pintype "passive"))
      (node (ref "R2") (pin "2") (pinfunction "2_2") (pintype "passive"))
      (node (ref "U2") (pin "22") (pinfunction "SET_OVCH_22") (pintype "bidirectional"))
    )
    (net (code "57") (name "Net-(U2-SET_OVDIS)") (class "Default")
      (node (ref "R3") (pin "1") (pinfunction "1_1") (pintype "passive"))
      (node (ref "R4") (pin "2") (pinfunction "2_2") (pintype "passive"))
      (node (ref "U2") (pin "24") (pinfunction "SET_OVDIS_24") (pintype "bidirectional"))
    )
    (net (code "58") (name "Net-(U2-SRC)") (class "Default")
      (node (ref "R10") (pin "1") (pinfunction "1_1") (pintype "passive"))
      (node (ref "U$16") (pin "P$2") (pinfunction "VOUT_P$2") (pintype "bidirectional"))
      (node (ref "U$16") (pin "P$3") (pinfunction "VOUT_P$3") (pintype "bidirectional"))
      (node (ref "U$36") (pin "P$1") (pinfunction "P$1_P$1") (pintype "bidirectional"))
      (node (ref "U$39") (pin "P$1") (pinfunction "P$1_P$1") (pintype "bidirectional"))
      (node (ref "U2") (pin "25") (pinfunction "SRC_25") (pintype "input"))
    )
    (net (code "59") (name "Net-(U2-STATUS1)") (class "Default")
      (node (ref "U$14") (pin "P$1") (pinfunction "P$1_P$1") (pintype "bidirectional"))
      (node (ref "U2") (pin "20") (pinfunction "STATUS1_20") (pintype "output"))
    )
    (net (code "60") (name "Net-(U2-STATUS2)") (class "Default")
      (node (ref "U$13") (pin "P$1") (pinfunction "P$1_P$1") (pintype "bidirectional"))
      (node (ref "U2") (pin "19") (pinfunction "STATUS2_19") (pintype "output"))
    )
    (net (code "61") (name "Net-(U2-SWBUCK)") (class "Default")
      (node (ref "U$1") (pin "2") (pinfunction "2_2") (pintype "passive"))
      (node (ref "U2") (pin "2") (pinfunction "SWBUCK_2") (pintype "bidirectional"))
    )
    (net (code "62") (name "unconnected-(U$10-P1-Pad1)") (class "Default")
      (node (ref "U$10") (pin "1") (pinfunction "P1_1") (pintype "bidirectional"))
    )
    (net (code "63") (name "unconnected-(U$10-P3-Pad3)") (class "Default")
      (node (ref "U$10") (pin "3") (pinfunction "P3_3") (pintype "bidirectional"))
    )
    (net (code "64") (name "unconnected-(U1-NC-Pad44)") (class "Default")
      (node (ref "U1") (pin "44") (pinfunction "NC_44") (pintype "bidirectional"))
    )
    (net (code "65") (name "unconnected-(U1-P19-Pad22)") (class "Default")
      (node (ref "U1") (pin "22") (pinfunction "P19_22") (pintype "bidirectional"))
    )
    (net (code "66") (name "unconnected-(U1-P20-Pad23)") (class "Default")
      (node (ref "U1") (pin "23") (pinfunction "P20_23") (pintype "bidirectional"))
    )
    (net (code "67") (name "unconnected-(U1-P22-Pad27)") (class "Default")
      (node (ref "U1") (pin "27") (pinfunction "P22_27") (pintype "bidirectional"))
    )
    (net (code "68") (name "unconnected-(U1-P23-Pad28)") (class "Default")
      (node (ref "U1") (pin "28") (pinfunction "P23_28") (pintype "bidirectional"))
    )
    (net (code "69") (name "unconnected-(U1-P24-Pad29)") (class "Default")
      (node (ref "U1") (pin "29") (pinfunction "P24_29") (pintype "bidirectional"))
    )
    (net (code "70") (name "unconnected-(U1-P25-Pad37)") (class "Default")
      (node (ref "U1") (pin "37") (pinfunction "P25_37") (pintype "bidirectional"))
    )
    (net (code "71") (name "unconnected-(U1-P26-Pad38)") (class "Default")
      (node (ref "U1") (pin "38") (pinfunction "P26_38") (pintype "bidirectional"))
    )
    (net (code "72") (name "unconnected-(U1-P27-Pad39)") (class "Default")
      (node (ref "U1") (pin "39") (pinfunction "P27_39") (pintype "bidirectional"))
    )
    (net (code "73") (name "unconnected-(U1-P28-Pad40)") (class "Default")
      (node (ref "U1") (pin "40") (pinfunction "P28_40") (pintype "bidirectional"))
    )
    (net (code "74") (name "unconnected-(U1-P29-Pad41)") (class "Default")
      (node (ref "U1") (pin "41") (pinfunction "P29_41") (pintype "bidirectional"))
    )
    (net (code "75") (name "unconnected-(U1-P30_AIN6-Pad42)") (class "Default")
      (node (ref "U1") (pin "42") (pinfunction "P30_AIN6_42") (pintype "bidirectional"))
    )
    (net (code "76") (name "unconnected-(U1-P31_AIN7-Pad43)") (class "Default")
      (node (ref "U1") (pin "43") (pinfunction "P31_AIN7_43") (pintype "bidirectional"))
    )
  )
)
